# EIS_Main_MSP430F6638.net
KiCad netlist of a schematic drawn in Altium Designer
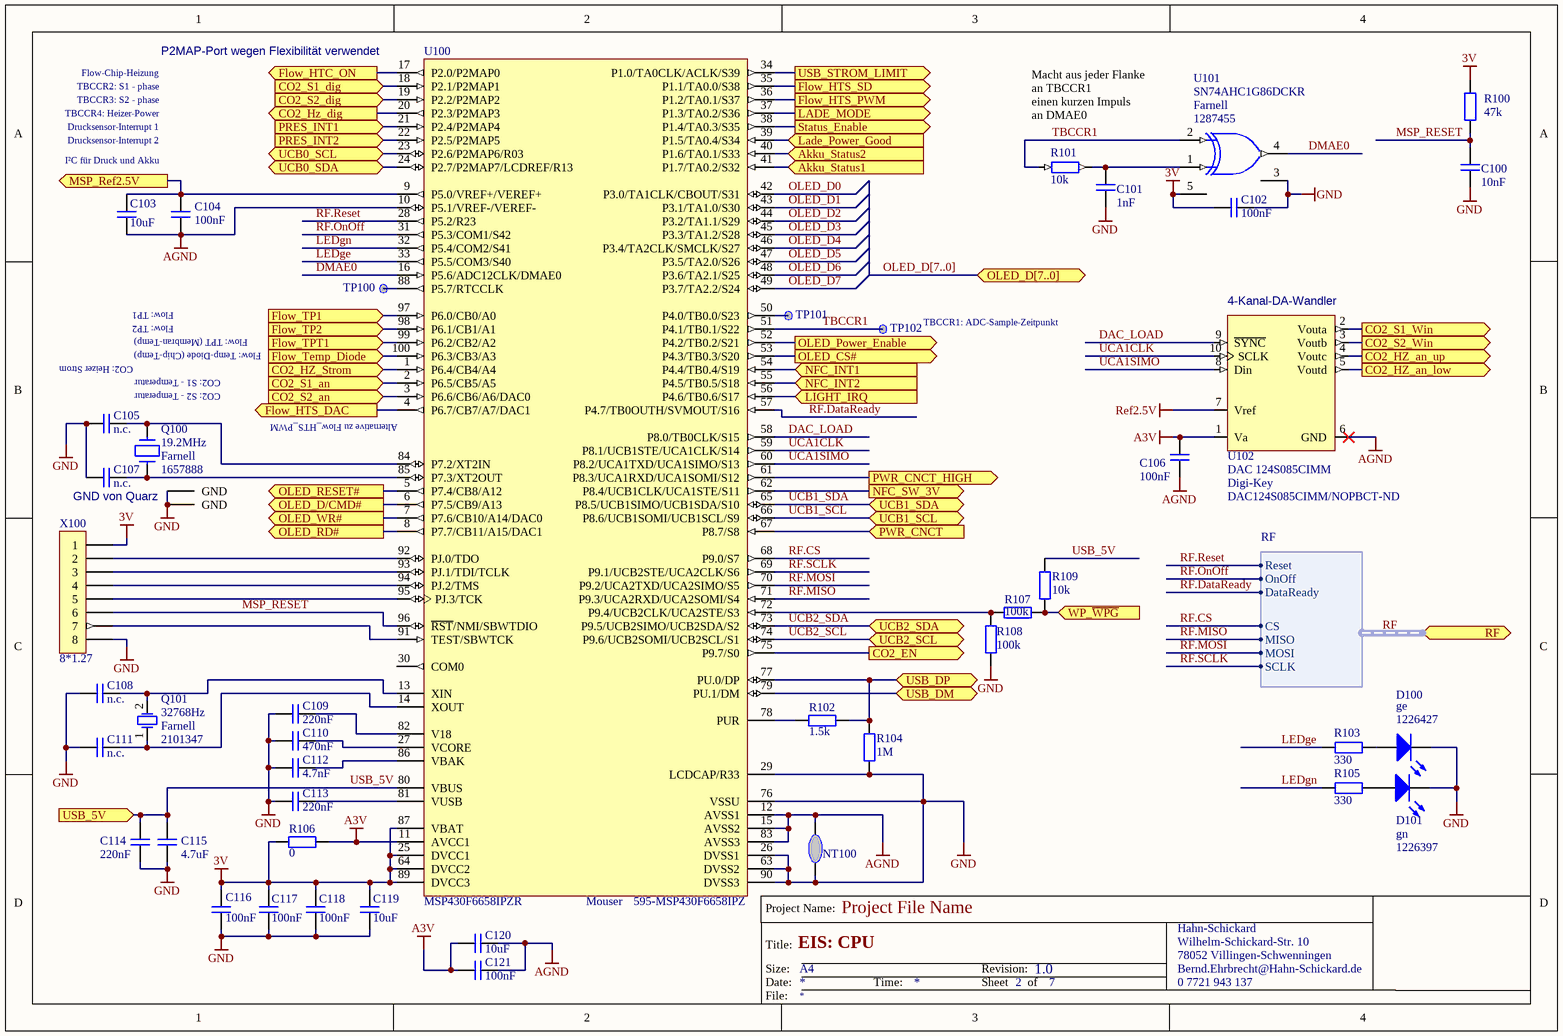
[diagram p0: EIS_Main_MSP430F6638.SchDoc]

(export (version "E")
  (design (tool "Eeschema 10.0.6"))
  (components
    (comp (ref "C100")
      (value "10nF")
      (footprint "CAPC1608N")
      (libsource (lib "My_Schlib_6_18") (part "Kondensator SMD Keramik"))
    )
    (comp (ref "C101")
      (value "1nF")
      (footprint "CAPC1608N")
      (libsource (lib "My_Schlib_6_18") (part "Kondensator SMD Keramik"))
    )
    (comp (ref "C102")
      (value "100nF")
      (footprint "CAPC1608N")
      (libsource (lib "My_Schlib_6_18") (part "Kondensator SMD Keramik"))
    )
    (comp (ref "C103")
      (value "10uF")
      (footprint "CAPC1608N")
      (libsource (lib "My_Schlib_6_15") (part "Kondensator SMD Keramik"))
    )
    (comp (ref "C104")
      (value "100nF")
      (footprint "CAPC1608N")
      (libsource (lib "My_Schlib_6_18") (part "Kondensator SMD Keramik"))
    )
    (comp (ref "C105")
      (value "n.c.")
      (footprint "CAPC1608N")
      (libsource (lib "My_Schlib_6_18") (part "Kondensator SMD Keramik"))
    )
    (comp (ref "C106")
      (value "100nF")
      (footprint "CAPC1608N")
      (libsource (lib "My_Schlib_6_15") (part "Kondensator SMD Keramik"))
    )
    (comp (ref "C107")
      (value "n.c.")
      (footprint "CAPC1608N")
      (libsource (lib "My_Schlib_6_18") (part "Kondensator SMD Keramik"))
    )
    (comp (ref "C108")
      (value "n.c.")
      (footprint "CAPC1608N")
      (libsource (lib "My_Schlib_6_18") (part "Kondensator SMD Keramik"))
    )
    (comp (ref "C109")
      (value "220nF")
      (footprint "CAPC1608N")
      (libsource (lib "My_Schlib_6_18") (part "Kondensator SMD Keramik"))
    )
    (comp (ref "C110")
      (value "470nF")
      (footprint "CAPC1608N")
      (libsource (lib "My_Schlib_6_15") (part "Kondensator SMD Keramik"))
    )
    (comp (ref "C111")
      (value "n.c.")
      (footprint "CAPC1608N")
      (libsource (lib "My_Schlib_6_18") (part "Kondensator SMD Keramik"))
    )
    (comp (ref "C112")
      (value "4.7nF")
      (footprint "CAPC1608N")
      (libsource (lib "My_Schlib_6_15") (part "Kondensator SMD Keramik"))
    )
    (comp (ref "C113")
      (value "220nF")
      (footprint "CAPC1608N")
      (libsource (lib "My_Schlib_6_18") (part "Kondensator SMD Keramik"))
    )
    (comp (ref "C114")
      (value "220nF")
      (footprint "CAPC1608N")
      (libsource (lib "My_Schlib_6_18") (part "Kondensator SMD Keramik"))
    )
    (comp (ref "C115")
      (value "4.7uF")
      (footprint "CAPC1608N")
      (libsource (lib "My_Schlib_6_18") (part "Kondensator SMD Keramik"))
    )
    (comp (ref "C116")
      (value "100nF")
      (footprint "CAPC1608N")
      (libsource (lib "My_Schlib_6_15") (part "Kondensator SMD Keramik"))
    )
    (comp (ref "C117")
      (value "100nF")
      (footprint "CAPC1608N")
      (libsource (lib "My_Schlib_6_15") (part "Kondensator SMD Keramik"))
    )
    (comp (ref "C118")
      (value "100nF")
      (footprint "CAPC1608N")
      (libsource (lib "My_Schlib_6_15") (part "Kondensator SMD Keramik"))
    )
    (comp (ref "C119")
      (value "10uF")
      (footprint "CAPC1608N")
      (libsource (lib "My_Schlib_6_15") (part "Kondensator SMD Keramik"))
    )
    (comp (ref "C120")
      (value "10uF")
      (footprint "CAPC1608N")
      (libsource (lib "My_Schlib_6_18") (part "Kondensator SMD Keramik"))
    )
    (comp (ref "C121")
      (value "100nF")
      (footprint "CAPC1608N")
      (libsource (lib "My_Schlib_6_15") (part "Kondensator SMD Keramik"))
    )
    (comp (ref "D100")
      (value "ge")
      (footprint "LED-Gelb")
      (fields (field (name "SUPPLIER PART NUMBER 1") "1226427"))
      (libsource (lib "My_Schlib_6_15") (part "LED SMD"))
    )
    (comp (ref "D101")
      (value "gn")
      (footprint "LED-gruen")
      (fields (field (name "SUPPLIER PART NUMBER 1") "1226397"))
      (libsource (lib "My_Schlib_6_15") (part "LED SMD"))
    )
    (comp (ref "NT100")
      (value "Net Tie without Boom")
      (footprint "NetTie")
      (fields (field (name "09_ERSTELLER") "HSG Jürgen Merz"))
      (libsource (lib "HSG-IMIT_JuergenMerz") (part "Net Tie without Boom"))
    )
    (comp (ref "Q100")
      (value "19.2MHz")
      (footprint "Quarz 4 Pin 2.5mm*2mm")
      (fields (field (name "SUPPLIER 1") "Farnell") (field (name "SUPPLIER PART NUMBER 1") "1657888"))
      (libsource (lib "My_Schlib_6_15") (part "QUARZ"))
    )
    (comp (ref "Q101")
      (value "32768Hz")
      (footprint "ABS07")
      (description "Uhren Quarz - Crystal")
      (fields
        (field (name "SUPPLIER 1") "Farnell")
        (field (name "SUPPLIER PART NUMBER 1") "2101347")
        (field (name "PUBLISHER") "Altium Limited")
      )
      (libsource (lib "MetaSensClampOn_BT") (part "XTAL"))
    )
    (comp (ref "R100")
      (value "47k")
      (footprint "RESC1608N")
      (libsource (lib "My_Schlib_6_15") (part "Widerstand SMD"))
    )
    (comp (ref "R101")
      (value "10k")
      (footprint "RESC1608N")
      (libsource (lib "My_Schlib_6_15") (part "Widerstand SMD"))
    )
    (comp (ref "R102")
      (value "1.5k")
      (footprint "RESC1608N")
      (description "Resistor")
      (fields (field (name "PUBLISHER") "Altium Limited"))
      (libsource (lib "Miscellaneous Devices") (part "Res2"))
    )
    (comp (ref "R103")
      (value "330")
      (footprint "RESC1608N")
      (libsource (lib "My_Schlib_6_15") (part "Widerstand SMD"))
    )
    (comp (ref "R104")
      (value "1M")
      (footprint "RESC1608N")
      (libsource (lib "My_Schlib_6_15") (part "Widerstand SMD"))
    )
    (comp (ref "R105")
      (value "330")
      (footprint "RESC1608N")
      (libsource (lib "My_Schlib_6_15") (part "Widerstand SMD"))
    )
    (comp (ref "R106")
      (value "0")
      (footprint "RESC1608N")
      (description "RESC1608 (R0603)")
      (libsource (lib "JM_Widerstaende") (part "RESC1608 (R0603)"))
    )
    (comp (ref "R107")
      (value "100k")
      (footprint "RESC1608N")
      (description "Resistor")
      (fields (field (name "PUBLISHER") "Altium Limited"))
      (libsource (lib "Miscellaneous Devices") (part "Res2"))
    )
    (comp (ref "R108")
      (value "100k")
      (footprint "RESC1608N")
      (description "Resistor")
      (fields (field (name "PUBLISHER") "Altium Limited"))
      (libsource (lib "") (part "Res2_1"))
    )
    (comp (ref "R109")
      (value "10k")
      (footprint "RESC1608N")
      (libsource (lib "My_Schlib_6_15") (part "Widerstand SMD"))
    )
    (comp (ref "TP100")
      (value "Testpoint 1mm")
      (footprint "Testpoint 1mm")
      (fields (field (name "PUBLISHER") "HSG Jürgen MErz"))
      (libsource (lib "MetaSensClampOn_BT") (part "Tespoint 1mm"))
    )
    (comp (ref "TP101")
      (value "Testpoint 1mm")
      (footprint "Testpoint 1mm")
      (fields (field (name "PUBLISHER") "HSG Jürgen MErz"))
      (libsource (lib "MetaSensClampOn_BT") (part "Tespoint 1mm"))
    )
    (comp (ref "TP102")
      (value "Testpoint 1mm")
      (footprint "Testpoint 1mm")
      (fields (field (name "PUBLISHER") "HSG Jürgen MErz"))
      (libsource (lib "MetaSensClampOn_BT") (part "Tespoint 1mm"))
    )
    (comp (ref "U100")
      (value "MSP430F6658IPZR")
      (footprint "TI-PZ100_N")
      (fields
        (field (name "MANUFACTURER") "Texas Instruments")
        (field (name "PARTNUMBER") "MSP430F6638IPZR")
        (field (name "SUPPLIER 1") "Mouser")
        (field (name "SUPPLIER PART NUMBER 1") "595-MSP430F6658IPZ")
      )
      (libsource (lib "Eis_Lib") (part "MSP430F6658IPZR"))
    )
    (comp (ref "U101")
      (value "SN74AHC1G86DCKR")
      (footprint "419A-01_N")
      (description "2-Input XOR Gate")
      (fields
        (field (name "SUPPLIER 1") "Farnell")
        (field (name "SUPPLIER PART NUMBER 1") "1287455")
        (field (name "PUBLISHER") "Altium Limited")
      )
      (libsource (lib "ON Semi Logic Gate") (part "MC74VHC1G86DFT1"))
    )
    (comp (ref "U102")
      (value "DAC 124S085CIMM")
      (footprint "MSOP-DGS")
      (description "DAC 4 Channel 12-Bit")
      (fields
        (field (name "SUPPLIER1") "Digi-Key")
        (field (name "SUPPLIER PART NUMBER 1") "DAC124S085CIMM/NOPBCT-ND")
      )
      (libsource (lib "MetaSensClampOn_BT") (part "DAC 124S085CIMM"))
    )
    (comp (ref "X100")
      (value "8*1.27")
      (footprint "JMP 8x1.27")
      (libsource (lib "My_Schlib_6_18") (part "JMP 8*1.27"))
    )
  )
  (nets
    (net (code "2") (name "/Akku_Status1") (class "Default")
      (node (ref "U100") (pin "41") (pinfunction "P1.7/TA0.2/S32_41") (pintype "input"))
    )
    (net (code "3") (name "/Akku_Status2") (class "Default")
      (node (ref "U100") (pin "40") (pinfunction "P1.6/TA0.1/S33_40") (pintype "input"))
    )
    (net (code "4") (name "/CO2_EN") (class "Default")
      (node (ref "U100") (pin "75") (pinfunction "P9.7/S0_75") (pintype "output"))
    )
    (net (code "5") (name "/CO2_HZ_Strom") (class "Default")
      (node (ref "U100") (pin "1") (pinfunction "P6.4/CB4/A4_1") (pintype "input"))
    )
    (net (code "6") (name "/CO2_HZ_an_low") (class "Default")
      (node (ref "U102") (pin "5") (pinfunction "Voutd_5") (pintype "output"))
    )
    (net (code "7") (name "/CO2_HZ_an_up") (class "Default")
      (node (ref "U102") (pin "4") (pinfunction "Voutc_4") (pintype "output"))
    )
    (net (code "8") (name "/CO2_Hz_dig") (class "Default")
      (node (ref "U100") (pin "20") (pinfunction "P2.3/P2MAP3_20") (pintype "output"))
    )
    (net (code "9") (name "/CO2_S1_Win") (class "Default")
      (node (ref "U102") (pin "2") (pinfunction "Vouta_2") (pintype "output"))
    )
    (net (code "10") (name "/CO2_S1_an") (class "Default")
      (node (ref "U100") (pin "2") (pinfunction "P6.5/CB5/A5_2") (pintype "input"))
    )
    (net (code "11") (name "/CO2_S1_dig") (class "Default")
      (node (ref "U100") (pin "18") (pinfunction "P2.1/P2MAP1_18") (pintype "input"))
    )
    (net (code "12") (name "/CO2_S2_Win") (class "Default")
      (node (ref "U102") (pin "3") (pinfunction "Voutb_3") (pintype "output"))
    )
    (net (code "13") (name "/CO2_S2_an") (class "Default")
      (node (ref "U100") (pin "3") (pinfunction "P6.6/CB6/A6/DAC0_3") (pintype "input"))
    )
    (net (code "14") (name "/CO2_S2_dig") (class "Default")
      (node (ref "U100") (pin "19") (pinfunction "P2.2/P2MAP2_19") (pintype "input"))
    )
    (net (code "15") (name "/DAC_LOAD") (class "Default")
      (node (ref "U100") (pin "58") (pinfunction "P8.0/TB0CLK/S15_58") (pintype "output"))
      (node (ref "U102") (pin "9") (pinfunction "~{SYNC}_9") (pintype "input"))
    )
    (net (code "16") (name "/DMAE0") (class "Default")
      (node (ref "U100") (pin "16") (pinfunction "P5.6/ADC12CLK/DMAE0_16") (pintype "input"))
      (node (ref "U101") (pin "4") (pinfunction "Y_4") (pintype "output"))
    )
    (net (code "17") (name "/Flow_HTC_ON") (class "Default")
      (node (ref "U100") (pin "17") (pinfunction "P2.0/P2MAP0_17") (pintype "output"))
    )
    (net (code "18") (name "/Flow_HTS_DAC") (class "Default")
      (node (ref "U100") (pin "4") (pinfunction "P6.7/CB7/A7/DAC1_4") (pintype "output"))
    )
    (net (code "19") (name "/Flow_HTS_PWM") (class "Default")
      (node (ref "U100") (pin "36") (pinfunction "P1.2/TA0.1/S37_36") (pintype "output"))
    )
    (net (code "20") (name "/Flow_HTS_SD") (class "Default")
      (node (ref "U100") (pin "35") (pinfunction "P1.1/TA0.0/S38_35") (pintype "output"))
    )
    (net (code "21") (name "/Flow_TP1") (class "Default")
      (node (ref "U100") (pin "97") (pinfunction "P6.0/CB0/A0_97") (pintype "input"))
    )
    (net (code "22") (name "/Flow_TP2") (class "Default")
      (node (ref "U100") (pin "98") (pinfunction "P6.1/CB1/A1_98") (pintype "input"))
    )
    (net (code "23") (name "/Flow_TPT1") (class "Default")
      (node (ref "U100") (pin "99") (pinfunction "P6.2/CB2/A2_99") (pintype "input"))
    )
    (net (code "24") (name "/Flow_Temp_Diode") (class "Default")
      (node (ref "U100") (pin "100") (pinfunction "P6.3/CB3/A3_100") (pintype "input"))
    )
    (net (code "25") (name "/LADE_MODE") (class "Default")
      (node (ref "U100") (pin "37") (pinfunction "P1.3/TA0.2/S36_37") (pintype "output"))
    )
    (net (code "26") (name "/LEDge") (class "Default")
      (node (ref "R103") (pin "2") (pinfunction "2_2") (pintype "passive"))
      (node (ref "U100") (pin "33") (pinfunction "P5.5/COM3/S40_33") (pintype "output"))
    )
    (net (code "27") (name "/LEDgn") (class "Default")
      (node (ref "R105") (pin "2") (pinfunction "2_2") (pintype "passive"))
      (node (ref "U100") (pin "32") (pinfunction "P5.4/COM2/S41_32") (pintype "output"))
    )
    (net (code "28") (name "/LIGHT_IRQ") (class "Default")
      (node (ref "U100") (pin "56") (pinfunction "P4.6/TB0.6/S17_56") (pintype "input"))
    )
    (net (code "29") (name "/Lade_Power_Good") (class "Default")
      (node (ref "U100") (pin "39") (pinfunction "P1.5/TA0.4/S34_39") (pintype "input"))
    )
    (net (code "30") (name "/MSP_RESET") (class "Default")
      (node (ref "C100") (pin "1") (pinfunction "1_1") (pintype "passive"))
      (node (ref "R100") (pin "1") (pinfunction "1_1") (pintype "passive"))
      (node (ref "U100") (pin "96") (pinfunction "~{RST}/NMI/SBWTDIO_96") (pintype "bidirectional"))
      (node (ref "X100") (pin "6") (pinfunction "6_6") (pintype "passive"))
    )
    (net (code "31") (name "/MSP_Ref2.5V") (class "Default")
      (node (ref "C103") (pin "1") (pinfunction "1_1") (pintype "passive"))
      (node (ref "C104") (pin "1") (pinfunction "1_1") (pintype "passive"))
      (node (ref "U100") (pin "9") (pinfunction "P5.0/VREF+/VEREF+_9") (pintype "output"))
    )
    (net (code "32") (name "/NFC_INT1") (class "Default")
      (node (ref "U100") (pin "54") (pinfunction "P4.4/TB0.4/S19_54") (pintype "input"))
    )
    (net (code "33") (name "/NFC_INT2") (class "Default")
      (node (ref "U100") (pin "55") (pinfunction "P4.5/TB0.5/S18_55") (pintype "input"))
    )
    (net (code "34") (name "/NFC_SW_3V") (class "Default")
      (node (ref "U100") (pin "62") (pinfunction "P8.4/UCB1CLK/UCA1STE/S11_62") (pintype "output"))
    )
    (net (code "35") (name "/OLED_CS#") (class "Default")
      (node (ref "U100") (pin "53") (pinfunction "P4.3/TB0.3/S20_53") (pintype "output"))
    )
    (net (code "36") (name "/OLED_D0") (class "Default")
      (node (ref "U100") (pin "42") (pinfunction "P3.0/TA1CLK/CBOUT/S31_42") (pintype "bidirectional"))
    )
    (net (code "37") (name "/OLED_D1") (class "Default")
      (node (ref "U100") (pin "43") (pinfunction "P3.1/TA1.0/S30_43") (pintype "bidirectional"))
    )
    (net (code "38") (name "/OLED_D2") (class "Default")
      (node (ref "U100") (pin "44") (pinfunction "P3.2/TA1.1/S29_44") (pintype "bidirectional"))
    )
    (net (code "39") (name "/OLED_D3") (class "Default")
      (node (ref "U100") (pin "45") (pinfunction "P3.3/TA1.2/S28_45") (pintype "bidirectional"))
    )
    (net (code "40") (name "/OLED_D4") (class "Default")
      (node (ref "U100") (pin "46") (pinfunction "P3.4/TA2CLK/SMCLK/S27_46") (pintype "bidirectional"))
    )
    (net (code "41") (name "/OLED_D5") (class "Default")
      (node (ref "U100") (pin "47") (pinfunction "P3.5/TA2.0/S26_47") (pintype "bidirectional"))
    )
    (net (code "42") (name "/OLED_D6") (class "Default")
      (node (ref "U100") (pin "48") (pinfunction "P3.6/TA2.1/S25_48") (pintype "bidirectional"))
    )
    (net (code "43") (name "/OLED_D7") (class "Default")
      (node (ref "U100") (pin "49") (pinfunction "P3.7/TA2.2/S24_49") (pintype "bidirectional"))
    )
    (net (code "45") (name "/OLED_D{slash}CMD#") (class "Default")
      (node (ref "U100") (pin "6") (pinfunction "P7.5/CB9/A13_6") (pintype "output"))
    )
    (net (code "46") (name "/OLED_Power_Enable") (class "Default")
      (node (ref "U100") (pin "52") (pinfunction "P4.2/TB0.2/S21_52") (pintype "output"))
    )
    (net (code "47") (name "/OLED_RD#") (class "Default")
      (node (ref "U100") (pin "8") (pinfunction "P7.7/CB11/A15/DAC1_8") (pintype "output"))
    )
    (net (code "48") (name "/OLED_RESET#") (class "Default")
      (node (ref "U100") (pin "5") (pinfunction "P7.4/CB8/A12_5") (pintype "output"))
    )
    (net (code "49") (name "/OLED_WR#") (class "Default")
      (node (ref "U100") (pin "7") (pinfunction "P7.6/CB10/A14/DAC0_7") (pintype "output"))
    )
    (net (code "50") (name "/PRES_INT1") (class "Default")
      (node (ref "U100") (pin "21") (pinfunction "P2.4/P2MAP4_21") (pintype "input"))
    )
    (net (code "51") (name "/PRES_INT2") (class "Default")
      (node (ref "U100") (pin "22") (pinfunction "P2.5/P2MAP5_22") (pintype "input"))
    )
    (net (code "52") (name "/PWR_CNCT") (class "Default")
      (node (ref "U100") (pin "67") (pinfunction "P8.7/S8_67") (pintype "input"))
    )
    (net (code "53") (name "/PWR_CNCT_HIGH") (class "Default")
      (node (ref "U100") (pin "61") (pinfunction "P8.3/UCA1RXD/UCA1SOMI/S12_61") (pintype "output"))
    )
    (net (code "54") (name "/RF.CS") (class "Default")
      (node (ref "U100") (pin "68") (pinfunction "P9.0/S7_68") (pintype "output"))
    )
    (net (code "55") (name "/RF.DataReady") (class "Default")
      (node (ref "U100") (pin "57") (pinfunction "P4.7/TB0OUTH/SVMOUT/S16_57") (pintype "input"))
    )
    (net (code "56") (name "/RF.MISO") (class "Default")
      (node (ref "U100") (pin "71") (pinfunction "P9.3/UCA2RXD/UCA2SOMI/S4_71") (pintype "input"))
    )
    (net (code "57") (name "/RF.MOSI") (class "Default")
      (node (ref "U100") (pin "70") (pinfunction "P9.2/UCA2TXD/UCA2SIMO/S5_70") (pintype "output"))
    )
    (net (code "58") (name "/RF.OnOff") (class "Default")
      (node (ref "U100") (pin "31") (pinfunction "P5.3/COM1/S42_31") (pintype "output"))
    )
    (net (code "59") (name "/RF.Reset") (class "Default")
      (node (ref "U100") (pin "28") (pinfunction "P5.2/R23_28") (pintype "output"))
    )
    (net (code "60") (name "/RF.SCLK") (class "Default")
      (node (ref "U100") (pin "69") (pinfunction "P9.1/UCB2STE/UCA2CLK/S6_69") (pintype "output"))
    )
    (net (code "62") (name "/Status_Enable") (class "Default")
      (node (ref "U100") (pin "38") (pinfunction "P1.4/TA0.3/S35_38") (pintype "output"))
    )
    (net (code "63") (name "/TBCCR1") (class "Default")
      (node (ref "R101") (pin "2") (pinfunction "2_2") (pintype "passive"))
      (node (ref "TP102") (pin "1") (pintype "passive"))
      (node (ref "U100") (pin "51") (pinfunction "P4.1/TB0.1/S22_51") (pintype "output"))
      (node (ref "U101") (pin "2") (pinfunction "A_2") (pintype "input"))
    )
    (net (code "64") (name "/UCA1CLK") (class "Default")
      (node (ref "U100") (pin "59") (pinfunction "P8.1/UCB1STE/UCA1CLK/S14_59") (pintype "output"))
      (node (ref "U102") (pin "10") (pinfunction "SCLK_10") (pintype "input"))
    )
    (net (code "65") (name "/UCA1SIMO") (class "Default")
      (node (ref "U100") (pin "60") (pinfunction "P8.2/UCA1TXD/UCA1SIMO/S13_60") (pintype "output"))
      (node (ref "U102") (pin "8") (pinfunction "Din_8") (pintype "input"))
    )
    (net (code "66") (name "/UCB0_SCL") (class "Default")
      (node (ref "U100") (pin "23") (pinfunction "P2.6/P2MAP6/R03_23") (pintype "bidirectional"))
    )
    (net (code "67") (name "/UCB0_SDA") (class "Default")
      (node (ref "U100") (pin "24") (pinfunction "P2.7/P2MAP7/LCDREF/R13_24") (pintype "bidirectional"))
    )
    (net (code "68") (name "/UCB1_SCL") (class "Default")
      (node (ref "U100") (pin "66") (pinfunction "P8.6/UCB1SOMI/UCB1SCL/S9_66") (pintype "bidirectional"))
    )
    (net (code "69") (name "/UCB1_SDA") (class "Default")
      (node (ref "U100") (pin "65") (pinfunction "P8.5/UCB1SIMO/UCB1SDA/S10_65") (pintype "bidirectional"))
    )
    (net (code "70") (name "/UCB2_SCL") (class "Default")
      (node (ref "U100") (pin "74") (pinfunction "P9.6/UCB2SOMI/UCB2SCL/S1_74") (pintype "bidirectional"))
    )
    (net (code "71") (name "/UCB2_SDA") (class "Default")
      (node (ref "U100") (pin "73") (pinfunction "P9.5/UCB2SIMO/UCB2SDA/S2_73") (pintype "bidirectional"))
    )
    (net (code "72") (name "/USB_5V") (class "Default")
      (node (ref "C114") (pin "1") (pinfunction "1_1") (pintype "passive"))
      (node (ref "C115") (pin "1") (pinfunction "1_1") (pintype "passive"))
      (node (ref "R109") (pin "1") (pinfunction "1_1") (pintype "passive"))
      (node (ref "U100") (pin "80") (pinfunction "VBUS_80") (pintype "passive"))
    )
    (net (code "73") (name "/USB_DM") (class "Default")
      (node (ref "U100") (pin "79") (pinfunction "PU.1/DM_79") (pintype "bidirectional"))
    )
    (net (code "74") (name "/USB_DP") (class "Default")
      (node (ref "R102") (pin "1") (pinfunction "1_1") (pintype "passive"))
      (node (ref "R104") (pin "2") (pinfunction "2_2") (pintype "passive"))
      (node (ref "U100") (pin "77") (pinfunction "PU.0/DP_77") (pintype "bidirectional"))
    )
    (net (code "75") (name "/USB_STROM_LIMIT") (class "Default")
      (node (ref "U100") (pin "34") (pinfunction "P1.0/TA0CLK/ACLK/S39_34") (pintype "output"))
    )
    (net (code "76") (name "/WP_~{WPG}") (class "Default")
      (node (ref "R107") (pin "1") (pinfunction "1_1") (pintype "passive"))
      (node (ref "R109") (pin "2") (pinfunction "2_2") (pintype "passive"))
    )
    (net (code "77") (name "3V") (class "Default")
      (node (ref "C102") (pin "1") (pinfunction "1_1") (pintype "passive"))
      (node (ref "C116") (pin "1") (pinfunction "1_1") (pintype "passive"))
      (node (ref "C117") (pin "1") (pinfunction "1_1") (pintype "passive"))
      (node (ref "C118") (pin "1") (pinfunction "1_1") (pintype "passive"))
      (node (ref "C119") (pin "1") (pinfunction "1_1") (pintype "passive"))
      (node (ref "R100") (pin "2") (pinfunction "2_2") (pintype "passive"))
      (node (ref "R106") (pin "1") (pinfunction "1_1") (pintype "passive"))
      (node (ref "U100") (pin "25") (pinfunction "DVCC1_25") (pintype "power_in"))
      (node (ref "U100") (pin "64") (pinfunction "DVCC2_64") (pintype "power_in"))
      (node (ref "U100") (pin "87") (pinfunction "VBAT_87") (pintype "power_in"))
      (node (ref "U100") (pin "89") (pinfunction "DVCC3_89") (pintype "power_in"))
      (node (ref "U101") (pin "5") (pinfunction "VDD_5") (pintype "power_in"))
      (node (ref "X100") (pin "1") (pinfunction "1_1") (pintype "passive"))
    )
    (net (code "78") (name "A3V") (class "Default")
      (node (ref "C106") (pin "2") (pinfunction "2_2") (pintype "passive"))
      (node (ref "C120") (pin "2") (pinfunction "2_2") (pintype "passive"))
      (node (ref "C121") (pin "1") (pinfunction "1_1") (pintype "passive"))
      (node (ref "R106") (pin "2") (pinfunction "2_2") (pintype "passive"))
      (node (ref "U100") (pin "11") (pinfunction "AVCC1_11") (pintype "power_in"))
      (node (ref "U102") (pin "1") (pinfunction "Va_1") (pintype "passive"))
    )
    (net (code "79") (name "AGND") (class "Default")
      (node (ref "C103") (pin "2") (pinfunction "2_2") (pintype "passive"))
      (node (ref "C104") (pin "2") (pinfunction "2_2") (pintype "passive"))
      (node (ref "C106") (pin "1") (pinfunction "1_1") (pintype "passive"))
      (node (ref "C120") (pin "1") (pinfunction "1_1") (pintype "passive"))
      (node (ref "C121") (pin "2") (pinfunction "2_2") (pintype "passive"))
      (node (ref "NT100") (pin "2") (pinfunction "2_2") (pintype "passive"))
      (node (ref "U100") (pin "10") (pinfunction "P5.1/VREF-/VEREF-_10") (pintype "bidirectional"))
      (node (ref "U100") (pin "12") (pinfunction "AVSS1_12") (pintype "power_in"))
      (node (ref "U100") (pin "15") (pinfunction "AVSS2_15") (pintype "power_in"))
      (node (ref "U100") (pin "83") (pinfunction "AVSS3_83") (pintype "power_in"))
      (node (ref "U102") (pin "6") (pinfunction "GND_6") (pintype "passive"))
    )
    (net (code "80") (name "GND") (class "Default")
      (node (ref "C100") (pin "2") (pinfunction "2_2") (pintype "passive"))
      (node (ref "C101") (pin "1") (pinfunction "1_1") (pintype "passive"))
      (node (ref "C102") (pin "2") (pinfunction "2_2") (pintype "passive"))
      (node (ref "C105") (pin "1") (pinfunction "1_1") (pintype "passive"))
      (node (ref "C107") (pin "1") (pinfunction "1_1") (pintype "passive"))
      (node (ref "C108") (pin "2") (pinfunction "2_2") (pintype "passive"))
      (node (ref "C109") (pin "1") (pinfunction "1_1") (pintype "passive"))
      (node (ref "C110") (pin "2") (pinfunction "2_2") (pintype "passive"))
      (node (ref "C111") (pin "1") (pinfunction "1_1") (pintype "passive"))
      (node (ref "C112") (pin "2") (pinfunction "2_2") (pintype "passive"))
      (node (ref "C113") (pin "1") (pinfunction "1_1") (pintype "passive"))
      (node (ref "C114") (pin "2") (pinfunction "2_2") (pintype "passive"))
      (node (ref "C115") (pin "2") (pinfunction "2_2") (pintype "passive"))
      (node (ref "C116") (pin "2") (pinfunction "2_2") (pintype "passive"))
      (node (ref "C117") (pin "2") (pinfunction "2_2") (pintype "passive"))
      (node (ref "C118") (pin "2") (pinfunction "2_2") (pintype "passive"))
      (node (ref "C119") (pin "2") (pinfunction "2_2") (pintype "passive"))
      (node (ref "D100") (pin "2") (pinfunction "2_2") (pintype "passive"))
      (node (ref "D101") (pin "2") (pinfunction "2_2") (pintype "passive"))
      (node (ref "NT100") (pin "1") (pinfunction "1_1") (pintype "passive"))
      (node (ref "Q100") (pin "2") (pinfunction "GND_2") (pintype "power_in"))
      (node (ref "Q100") (pin "4") (pinfunction "GND_4") (pintype "power_in"))
      (node (ref "R104") (pin "1") (pinfunction "1_1") (pintype "passive"))
      (node (ref "R108") (pin "1") (pinfunction "1_1") (pintype "passive"))
      (node (ref "U100") (pin "26") (pinfunction "DVSS1_26") (pintype "power_in"))
      (node (ref "U100") (pin "29") (pinfunction "LCDCAP/R33_29") (pintype "passive"))
      (node (ref "U100") (pin "63") (pinfunction "DVSS2_63") (pintype "power_in"))
      (node (ref "U100") (pin "76") (pinfunction "VSSU_76") (pintype "power_in"))
      (node (ref "U100") (pin "90") (pinfunction "DVSS3_90") (pintype "power_in"))
      (node (ref "U101") (pin "3") (pinfunction "GND_3") (pintype "power_in"))
      (node (ref "X100") (pin "8") (pinfunction "8_8") (pintype "passive"))
    )
    (net (code "81") (name "Net-(D100-Pad1)") (class "Default")
      (node (ref "D100") (pin "1") (pinfunction "1_1") (pintype "passive"))
      (node (ref "R103") (pin "1") (pinfunction "1_1") (pintype "passive"))
    )
    (net (code "82") (name "Net-(D101-Pad1)") (class "Default")
      (node (ref "D101") (pin "1") (pinfunction "1_1") (pintype "passive"))
      (node (ref "R105") (pin "1") (pinfunction "1_1") (pintype "passive"))
    )
    (net (code "83") (name "Net-(Q101-OSC1)") (class "Default")
      (node (ref "C111") (pin "2") (pinfunction "2_2") (pintype "passive"))
      (node (ref "Q101") (pin "1") (pinfunction "OSC1_1") (pintype "passive"))
      (node (ref "U100") (pin "14") (pinfunction "XOUT_14") (pintype "passive"))
    )
    (net (code "84") (name "Net-(Q101-OSC2)") (class "Default")
      (node (ref "C108") (pin "1") (pinfunction "1_1") (pintype "passive"))
      (node (ref "Q101") (pin "2") (pinfunction "OSC2_2") (pintype "passive"))
      (node (ref "U100") (pin "13") (pinfunction "XIN_13") (pintype "passive"))
    )
    (net (code "85") (name "Net-(U100-P4.0{slash}TB0.0{slash}S23)") (class "Default")
      (node (ref "TP101") (pin "1") (pintype "passive"))
      (node (ref "U100") (pin "50") (pinfunction "P4.0/TB0.0/S23_50") (pintype "output"))
    )
    (net (code "86") (name "Net-(U100-P5.7{slash}RTCCLK)") (class "Default")
      (node (ref "TP100") (pin "1") (pintype "passive"))
      (node (ref "U100") (pin "88") (pinfunction "P5.7/RTCCLK_88") (pintype "output"))
    )
    (net (code "87") (name "Net-(U100-P7.2{slash}XT2IN)") (class "Default")
      (node (ref "C105") (pin "2") (pinfunction "2_2") (pintype "passive"))
      (node (ref "Q100") (pin "3") (pinfunction "3_3") (pintype "passive"))
      (node (ref "U100") (pin "84") (pinfunction "P7.2/XT2IN_84") (pintype "bidirectional"))
    )
    (net (code "88") (name "Net-(U100-P7.3{slash}XT2OUT)") (class "Default")
      (node (ref "C107") (pin "2") (pinfunction "2_2") (pintype "passive"))
      (node (ref "Q100") (pin "1") (pinfunction "1_1") (pintype "passive"))
      (node (ref "U100") (pin "85") (pinfunction "P7.3/XT2OUT_85") (pintype "bidirectional"))
    )
    (net (code "89") (name "Net-(U100-P9.4{slash}UCB2CLK{slash}UCA2STE{slash}S3)") (class "Default")
      (node (ref "R107") (pin "2") (pinfunction "2_2") (pintype "passive"))
      (node (ref "R108") (pin "2") (pinfunction "2_2") (pintype "passive"))
      (node (ref "U100") (pin "72") (pinfunction "P9.4/UCB2CLK/UCA2STE/S3_72") (pintype "input"))
    )
    (net (code "90") (name "Net-(U100-PJ.0{slash}TDO)") (class "Default")
      (node (ref "U100") (pin "92") (pinfunction "PJ.0/TDO_92") (pintype "bidirectional"))
      (node (ref "X100") (pin "2") (pinfunction "2_2") (pintype "passive"))
    )
    (net (code "91") (name "Net-(U100-PJ.1{slash}TDI{slash}TCLK)") (class "Default")
      (node (ref "U100") (pin "93") (pinfunction "PJ.1/TDI/TCLK_93") (pintype "bidirectional"))
      (node (ref "X100") (pin "3") (pinfunction "3_3") (pintype "passive"))
    )
    (net (code "92") (name "Net-(U100-PJ.2{slash}TMS)") (class "Default")
      (node (ref "U100") (pin "94") (pinfunction "PJ.2/TMS_94") (pintype "bidirectional"))
      (node (ref "X100") (pin "4") (pinfunction "4_4") (pintype "passive"))
    )
    (net (code "93") (name "Net-(U100-PJ.3{slash}TCK)") (class "Default")
      (node (ref "U100") (pin "95") (pinfunction "PJ.3/TCK_95") (pintype "bidirectional"))
      (node (ref "X100") (pin "5") (pinfunction "5_5") (pintype "passive"))
    )
    (net (code "94") (name "Net-(U100-PUR)") (class "Default")
      (node (ref "R102") (pin "2") (pinfunction "2_2") (pintype "passive"))
      (node (ref "U100") (pin "78") (pinfunction "PUR_78") (pintype "passive"))
    )
    (net (code "95") (name "Net-(U100-TEST{slash}SBWTCK)") (class "Default")
      (node (ref "U100") (pin "91") (pinfunction "TEST/SBWTCK_91") (pintype "input"))
      (node (ref "X100") (pin "7") (pinfunction "7_7") (pintype "output"))
    )
    (net (code "96") (name "Net-(U100-V18)") (class "Default")
      (node (ref "C109") (pin "2") (pinfunction "2_2") (pintype "passive"))
      (node (ref "U100") (pin "82") (pinfunction "V18_82") (pintype "passive"))
    )
    (net (code "97") (name "Net-(U100-VBAK)") (class "Default")
      (node (ref "C112") (pin "1") (pinfunction "1_1") (pintype "passive"))
      (node (ref "U100") (pin "86") (pinfunction "VBAK_86") (pintype "passive"))
    )
    (net (code "98") (name "Net-(U100-VCORE)") (class "Default")
      (node (ref "C110") (pin "1") (pinfunction "1_1") (pintype "passive"))
      (node (ref "U100") (pin "27") (pinfunction "VCORE_27") (pintype "passive"))
    )
    (net (code "99") (name "Net-(U100-VUSB)") (class "Default")
      (node (ref "C113") (pin "2") (pinfunction "2_2") (pintype "passive"))
      (node (ref "U100") (pin "81") (pinfunction "VUSB_81") (pintype "power_in"))
    )
    (net (code "100") (name "Net-(U101-B)") (class "Default")
      (node (ref "C101") (pin "2") (pinfunction "2_2") (pintype "passive"))
      (node (ref "R101") (pin "1") (pinfunction "1_1") (pintype "passive"))
      (node (ref "U101") (pin "1") (pinfunction "B_1") (pintype "input"))
    )
    (net (code "101") (name "Ref2.5V") (class "Default")
      (node (ref "U102") (pin "7") (pinfunction "Vref_7") (pintype "passive"))
    )
    (net (code "102") (name "unconnected-(U100-COM0-Pad30)") (class "Default")
      (node (ref "U100") (pin "30") (pinfunction "COM0_30") (pintype "output"))
    )
  )
)
